# Hub.net
KiCad netlist of a schematic drawn in EAGLE
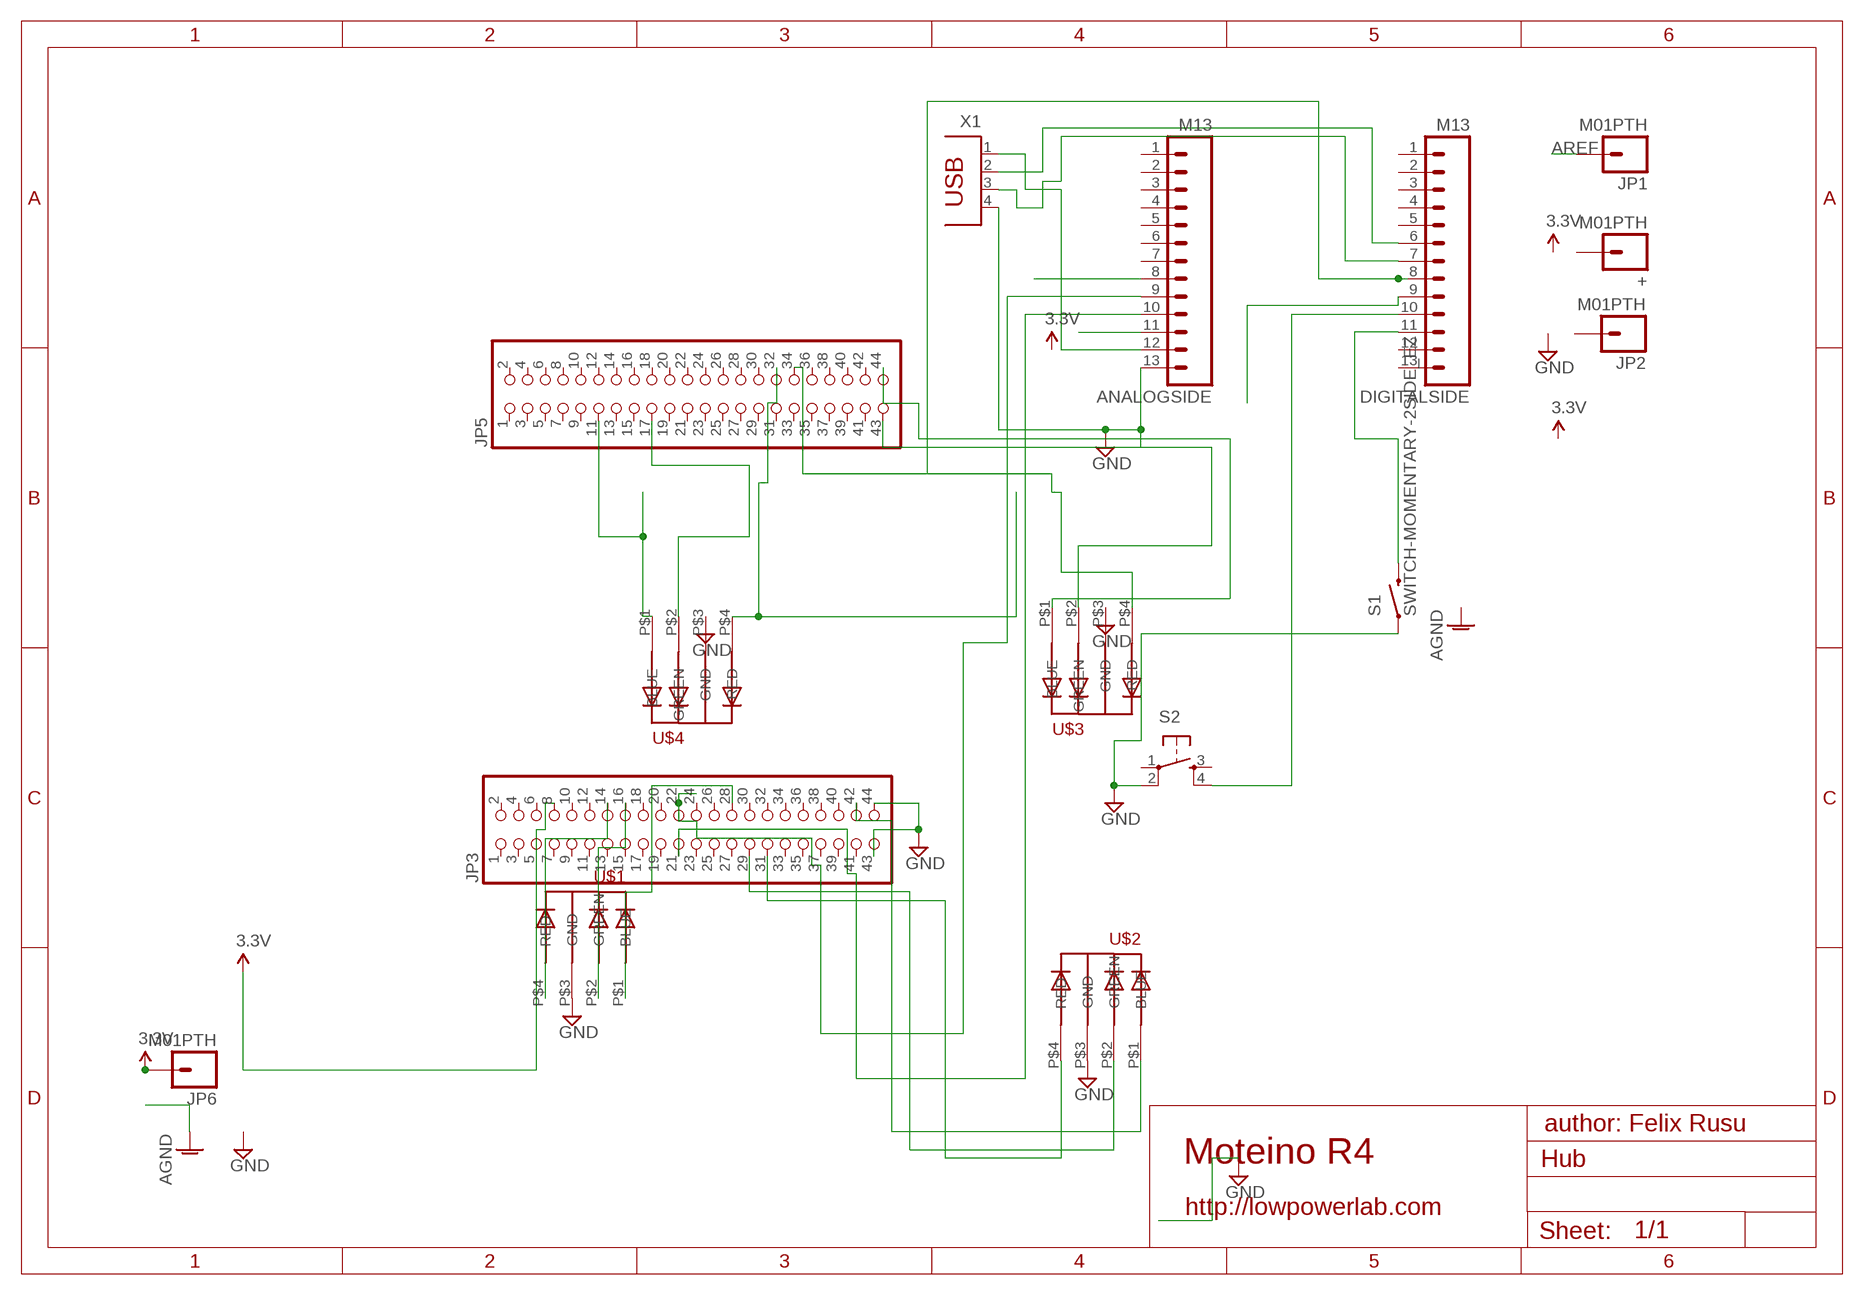
[diagram p0: schematic, sheet 1]

(export (version "E")
  (design (tool "Eeschema 10.0.6"))
  (components
    (comp (ref "+")
      (value "M01PTH")
      (footprint "eagle-import:1X01")
      (libsource (lib "eagle-import") (part "M01PTH"))
    )
    (comp (ref "ANALOGSIDE")
      (value "M13")
      (footprint "eagle-import:1X13")
      (libsource (lib "eagle-import") (part "M13"))
    )
    (comp (ref "DIGITALSIDE")
      (value "M13")
      (footprint "eagle-import:1X13")
      (libsource (lib "eagle-import") (part "M13"))
    )
    (comp (ref "JP1")
      (value "M01PTH")
      (footprint "eagle-import:1X01")
      (libsource (lib "eagle-import") (part "M01PTH"))
    )
    (comp (ref "JP2")
      (value "M01PTH")
      (footprint "eagle-import:1X01")
      (libsource (lib "eagle-import") (part "M01PTH"))
    )
    (comp (ref "JP3")
      (value "PINHD-2X22")
      (footprint "eagle-import:2X22")
      (libsource (lib "eagle-import") (part "PINHD-2X22"))
    )
    (comp (ref "JP5")
      (value "PINHD-2X22")
      (footprint "eagle-import:2X22")
      (libsource (lib "eagle-import") (part "PINHD-2X22"))
    )
    (comp (ref "JP6")
      (value "M01PTH")
      (footprint "eagle-import:1X01")
      (libsource (lib "eagle-import") (part "M01PTH"))
    )
    (comp (ref "S1")
      (value "SWITCH-MOMENTARY-2SIDE_EZ")
      (footprint "eagle-import:TACTILE-PTH-SIDEEZ")
      (libsource (lib "eagle-import") (part "SWITCH-MOMENTARY-2SIDE_EZ"))
    )
    (comp (ref "S2")
      (value "TAC_SWITCHPTH")
      (footprint "eagle-import:TACTILE-PTH")
      (libsource (lib "eagle-import") (part "TAC_SWITCHPTH"))
    )
    (comp (ref "U$1")
      (value "5MMRGBLED")
      (footprint "eagle-import:LED5MMRGB")
      (libsource (lib "eagle-import") (part "5MMRGBLED"))
    )
    (comp (ref "U$2")
      (value "5MMRGBLED")
      (footprint "eagle-import:LED5MMRGB")
      (libsource (lib "eagle-import") (part "5MMRGBLED"))
    )
    (comp (ref "U$3")
      (value "5MMRGBLED")
      (footprint "eagle-import:LED5MMRGB")
      (libsource (lib "eagle-import") (part "5MMRGBLED"))
    )
    (comp (ref "U$4")
      (value "5MMRGBLED")
      (footprint "eagle-import:LED5MMRGB")
      (libsource (lib "eagle-import") (part "5MMRGBLED"))
    )
    (comp (ref "X1")
      (value "PN87520")
      (footprint "eagle-import:PN87520")
      (libsource (lib "eagle-import") (part "PN87520"))
    )
  )
  (nets
    (net (code "1") (name "/AREF") (class "Default")
      (node (ref "JP1") (pin "1") (pinfunction "1_1") (pintype "passive"))
    )
    (net (code "2") (name "3.3V") (class "Default")
      (node (ref "JP3") (pin "8") (pinfunction "8_8") (pintype "passive"))
      (node (ref "JP6") (pin "1") (pinfunction "1_1") (pintype "passive"))
    )
    (net (code "4") (name "GND") (class "Default")
      (node (ref "ANALOGSIDE") (pin "13") (pinfunction "13_13") (pintype "passive"))
      (node (ref "JP3") (pin "43") (pinfunction "43_43") (pintype "passive"))
      (node (ref "JP3") (pin "44") (pinfunction "44_44") (pintype "passive"))
      (node (ref "S1") (pin "1") (pinfunction "1_1") (pintype "passive"))
      (node (ref "S2") (pin "2") (pinfunction "2_2") (pintype "passive"))
      (node (ref "U$1") (pin "P$3") (pinfunction "GND_P$3") (pintype "bidirectional"))
      (node (ref "U$2") (pin "P$3") (pinfunction "GND_P$3") (pintype "bidirectional"))
      (node (ref "U$3") (pin "P$3") (pinfunction "GND_P$3") (pintype "bidirectional"))
      (node (ref "U$4") (pin "P$3") (pinfunction "GND_P$3") (pintype "bidirectional"))
      (node (ref "X1") (pin "4") (pinfunction "4_4") (pintype "passive"))
    )
    (net (code "5") (name "Net-(ANALOGSIDE-Pad9)") (class "Default")
      (node (ref "ANALOGSIDE") (pin "9") (pinfunction "9_9") (pintype "passive"))
      (node (ref "JP3") (pin "22") (pinfunction "22_22") (pintype "passive"))
    )
    (net (code "6") (name "Net-(ANALOGSIDE-Pad10)") (class "Default")
      (node (ref "ANALOGSIDE") (pin "10") (pinfunction "10_10") (pintype "passive"))
      (node (ref "JP3") (pin "21") (pinfunction "21_21") (pintype "passive"))
    )
    (net (code "7") (name "Net-(ANALOGSIDE-Pad12)") (class "Default")
      (node (ref "ANALOGSIDE") (pin "12") (pinfunction "12_12") (pintype "passive"))
      (node (ref "X1") (pin "1") (pinfunction "1_1") (pintype "passive"))
    )
    (net (code "8") (name "Net-(DIGITALSIDE-Pad6)") (class "Default")
      (node (ref "DIGITALSIDE") (pin "6") (pinfunction "6_6") (pintype "passive"))
      (node (ref "X1") (pin "2") (pinfunction "2_2") (pintype "passive"))
    )
    (net (code "9") (name "Net-(DIGITALSIDE-Pad7)") (class "Default")
      (node (ref "DIGITALSIDE") (pin "7") (pinfunction "7_7") (pintype "passive"))
      (node (ref "X1") (pin "3") (pinfunction "3_3") (pintype "passive"))
    )
    (net (code "10") (name "Net-(DIGITALSIDE-Pad10)") (class "Default")
      (node (ref "DIGITALSIDE") (pin "10") (pinfunction "10_10") (pintype "passive"))
      (node (ref "S2") (pin "4") (pinfunction "4_4") (pintype "passive"))
    )
    (net (code "11") (name "Net-(DIGITALSIDE-Pad11)") (class "Default")
      (node (ref "DIGITALSIDE") (pin "11") (pinfunction "11_11") (pintype "passive"))
      (node (ref "S1") (pin "2") (pinfunction "2_2") (pintype "passive"))
    )
    (net (code "12") (name "Net-(U$1-BLUE)") (class "Default")
      (node (ref "JP3") (pin "28") (pinfunction "28_28") (pintype "passive"))
      (node (ref "U$1") (pin "P$1") (pinfunction "BLUE_P$1") (pintype "bidirectional"))
    )
    (net (code "13") (name "Net-(U$1-GREEN)") (class "Default")
      (node (ref "JP3") (pin "16") (pinfunction "16_16") (pintype "passive"))
      (node (ref "U$1") (pin "P$2") (pinfunction "GREEN_P$2") (pintype "bidirectional"))
    )
    (net (code "14") (name "Net-(U$1-RED)") (class "Default")
      (node (ref "JP3") (pin "14") (pinfunction "14_14") (pintype "passive"))
      (node (ref "U$1") (pin "P$4") (pinfunction "RED_P$4") (pintype "bidirectional"))
    )
    (net (code "15") (name "Net-(U$2-BLUE)") (class "Default")
      (node (ref "JP3") (pin "42") (pinfunction "42_42") (pintype "passive"))
      (node (ref "U$2") (pin "P$1") (pinfunction "BLUE_P$1") (pintype "bidirectional"))
    )
    (net (code "16") (name "Net-(U$2-GREEN)") (class "Default")
      (node (ref "JP3") (pin "29") (pinfunction "29_29") (pintype "passive"))
      (node (ref "U$2") (pin "P$2") (pinfunction "GREEN_P$2") (pintype "bidirectional"))
    )
    (net (code "17") (name "Net-(U$2-RED)") (class "Default")
      (node (ref "JP3") (pin "31") (pinfunction "31_31") (pintype "passive"))
      (node (ref "U$2") (pin "P$4") (pinfunction "RED_P$4") (pintype "bidirectional"))
    )
    (net (code "18") (name "Net-(U$3-BLUE)") (class "Default")
      (node (ref "JP5") (pin "44") (pinfunction "44_44") (pintype "passive"))
      (node (ref "U$3") (pin "P$1") (pinfunction "BLUE_P$1") (pintype "bidirectional"))
    )
    (net (code "19") (name "Net-(U$3-GREEN)") (class "Default")
      (node (ref "JP5") (pin "43") (pinfunction "43_43") (pintype "passive"))
      (node (ref "U$3") (pin "P$2") (pinfunction "GREEN_P$2") (pintype "bidirectional"))
    )
    (net (code "20") (name "Net-(U$3-RED)") (class "Default")
      (node (ref "JP5") (pin "34") (pinfunction "34_34") (pintype "passive"))
      (node (ref "U$3") (pin "P$4") (pinfunction "RED_P$4") (pintype "bidirectional"))
    )
    (net (code "21") (name "Net-(U$4-BLUE)") (class "Default")
      (node (ref "JP5") (pin "11") (pinfunction "11_11") (pintype "passive"))
      (node (ref "U$4") (pin "P$1") (pinfunction "BLUE_P$1") (pintype "bidirectional"))
    )
    (net (code "22") (name "Net-(U$4-GREEN)") (class "Default")
      (node (ref "JP5") (pin "17") (pinfunction "17_17") (pintype "passive"))
      (node (ref "U$4") (pin "P$2") (pinfunction "GREEN_P$2") (pintype "bidirectional"))
    )
    (net (code "23") (name "Net-(U$4-RED)") (class "Default")
      (node (ref "JP5") (pin "32") (pinfunction "32_32") (pintype "passive"))
      (node (ref "U$4") (pin "P$4") (pinfunction "RED_P$4") (pintype "bidirectional"))
    )
    (net (code "24") (name "unconnected-(+-Pad1)") (class "Default")
      (node (ref "+") (pin "1") (pinfunction "1_1") (pintype "passive"))
    )
    (net (code "25") (name "unconnected-(ANALOGSIDE-Pad1)") (class "Default")
      (node (ref "ANALOGSIDE") (pin "1") (pinfunction "1_1") (pintype "passive"))
    )
    (net (code "26") (name "unconnected-(ANALOGSIDE-Pad2)") (class "Default")
      (node (ref "ANALOGSIDE") (pin "2") (pinfunction "2_2") (pintype "passive"))
    )
    (net (code "27") (name "unconnected-(ANALOGSIDE-Pad3)") (class "Default")
      (node (ref "ANALOGSIDE") (pin "3") (pinfunction "3_3") (pintype "passive"))
    )
    (net (code "28") (name "unconnected-(ANALOGSIDE-Pad4)") (class "Default")
      (node (ref "ANALOGSIDE") (pin "4") (pinfunction "4_4") (pintype "passive"))
    )
    (net (code "29") (name "unconnected-(ANALOGSIDE-Pad5)") (class "Default")
      (node (ref "ANALOGSIDE") (pin "5") (pinfunction "5_5") (pintype "passive"))
    )
    (net (code "30") (name "unconnected-(ANALOGSIDE-Pad6)") (class "Default")
      (node (ref "ANALOGSIDE") (pin "6") (pinfunction "6_6") (pintype "passive"))
    )
    (net (code "31") (name "unconnected-(ANALOGSIDE-Pad7)") (class "Default")
      (node (ref "ANALOGSIDE") (pin "7") (pinfunction "7_7") (pintype "passive"))
    )
    (net (code "32") (name "unconnected-(ANALOGSIDE-Pad8)") (class "Default")
      (node (ref "ANALOGSIDE") (pin "8") (pinfunction "8_8") (pintype "passive"))
    )
    (net (code "33") (name "unconnected-(ANALOGSIDE-Pad11)") (class "Default")
      (node (ref "ANALOGSIDE") (pin "11") (pinfunction "11_11") (pintype "passive"))
    )
    (net (code "34") (name "unconnected-(DIGITALSIDE-Pad1)") (class "Default")
      (node (ref "DIGITALSIDE") (pin "1") (pinfunction "1_1") (pintype "passive"))
    )
    (net (code "35") (name "unconnected-(DIGITALSIDE-Pad2)") (class "Default")
      (node (ref "DIGITALSIDE") (pin "2") (pinfunction "2_2") (pintype "passive"))
    )
    (net (code "36") (name "unconnected-(DIGITALSIDE-Pad3)") (class "Default")
      (node (ref "DIGITALSIDE") (pin "3") (pinfunction "3_3") (pintype "passive"))
    )
    (net (code "37") (name "unconnected-(DIGITALSIDE-Pad4)") (class "Default")
      (node (ref "DIGITALSIDE") (pin "4") (pinfunction "4_4") (pintype "passive"))
    )
    (net (code "38") (name "unconnected-(DIGITALSIDE-Pad5)") (class "Default")
      (node (ref "DIGITALSIDE") (pin "5") (pinfunction "5_5") (pintype "passive"))
    )
    (net (code "39") (name "unconnected-(DIGITALSIDE-Pad8)") (class "Default")
      (node (ref "DIGITALSIDE") (pin "8") (pinfunction "8_8") (pintype "passive"))
    )
    (net (code "40") (name "unconnected-(DIGITALSIDE-Pad9)") (class "Default")
      (node (ref "DIGITALSIDE") (pin "9") (pinfunction "9_9") (pintype "passive"))
    )
    (net (code "41") (name "unconnected-(DIGITALSIDE-Pad12)") (class "Default")
      (node (ref "DIGITALSIDE") (pin "12") (pinfunction "12_12") (pintype "passive"))
    )
    (net (code "42") (name "unconnected-(DIGITALSIDE-Pad13)") (class "Default")
      (node (ref "DIGITALSIDE") (pin "13") (pinfunction "13_13") (pintype "passive"))
    )
    (net (code "43") (name "unconnected-(JP2-Pad1)") (class "Default")
      (node (ref "JP2") (pin "1") (pinfunction "1_1") (pintype "passive"))
    )
    (net (code "44") (name "unconnected-(JP3-Pad1)") (class "Default")
      (node (ref "JP3") (pin "1") (pinfunction "1_1") (pintype "passive"))
    )
    (net (code "45") (name "unconnected-(JP3-Pad2)") (class "Default")
      (node (ref "JP3") (pin "2") (pinfunction "2_2") (pintype "passive"))
    )
    (net (code "46") (name "unconnected-(JP3-Pad3)") (class "Default")
      (node (ref "JP3") (pin "3") (pinfunction "3_3") (pintype "passive"))
    )
    (net (code "47") (name "unconnected-(JP3-Pad4)") (class "Default")
      (node (ref "JP3") (pin "4") (pinfunction "4_4") (pintype "passive"))
    )
    (net (code "48") (name "unconnected-(JP3-Pad5)") (class "Default")
      (node (ref "JP3") (pin "5") (pinfunction "5_5") (pintype "passive"))
    )
    (net (code "49") (name "unconnected-(JP3-Pad6)") (class "Default")
      (node (ref "JP3") (pin "6") (pinfunction "6_6") (pintype "passive"))
    )
    (net (code "50") (name "unconnected-(JP3-Pad7)") (class "Default")
      (node (ref "JP3") (pin "7") (pinfunction "7_7") (pintype "passive"))
    )
    (net (code "51") (name "unconnected-(JP3-Pad9)") (class "Default")
      (node (ref "JP3") (pin "9") (pinfunction "9_9") (pintype "passive"))
    )
    (net (code "52") (name "unconnected-(JP3-Pad10)") (class "Default")
      (node (ref "JP3") (pin "10") (pinfunction "10_10") (pintype "passive"))
    )
    (net (code "53") (name "unconnected-(JP3-Pad11)") (class "Default")
      (node (ref "JP3") (pin "11") (pinfunction "11_11") (pintype "passive"))
    )
    (net (code "54") (name "unconnected-(JP3-Pad12)") (class "Default")
      (node (ref "JP3") (pin "12") (pinfunction "12_12") (pintype "passive"))
    )
    (net (code "55") (name "unconnected-(JP3-Pad13)") (class "Default")
      (node (ref "JP3") (pin "13") (pinfunction "13_13") (pintype "passive"))
    )
    (net (code "56") (name "unconnected-(JP3-Pad15)") (class "Default")
      (node (ref "JP3") (pin "15") (pinfunction "15_15") (pintype "passive"))
    )
    (net (code "57") (name "unconnected-(JP3-Pad17)") (class "Default")
      (node (ref "JP3") (pin "17") (pinfunction "17_17") (pintype "passive"))
    )
    (net (code "58") (name "unconnected-(JP3-Pad18)") (class "Default")
      (node (ref "JP3") (pin "18") (pinfunction "18_18") (pintype "passive"))
    )
    (net (code "59") (name "unconnected-(JP3-Pad19)") (class "Default")
      (node (ref "JP3") (pin "19") (pinfunction "19_19") (pintype "passive"))
    )
    (net (code "60") (name "unconnected-(JP3-Pad20)") (class "Default")
      (node (ref "JP3") (pin "20") (pinfunction "20_20") (pintype "passive"))
    )
    (net (code "61") (name "unconnected-(JP3-Pad23)") (class "Default")
      (node (ref "JP3") (pin "23") (pinfunction "23_23") (pintype "passive"))
    )
    (net (code "62") (name "unconnected-(JP3-Pad24)") (class "Default")
      (node (ref "JP3") (pin "24") (pinfunction "24_24") (pintype "passive"))
    )
    (net (code "63") (name "unconnected-(JP3-Pad25)") (class "Default")
      (node (ref "JP3") (pin "25") (pinfunction "25_25") (pintype "passive"))
    )
    (net (code "64") (name "unconnected-(JP3-Pad26)") (class "Default")
      (node (ref "JP3") (pin "26") (pinfunction "26_26") (pintype "passive"))
    )
    (net (code "65") (name "unconnected-(JP3-Pad27)") (class "Default")
      (node (ref "JP3") (pin "27") (pinfunction "27_27") (pintype "passive"))
    )
    (net (code "66") (name "unconnected-(JP3-Pad30)") (class "Default")
      (node (ref "JP3") (pin "30") (pinfunction "30_30") (pintype "passive"))
    )
    (net (code "67") (name "unconnected-(JP3-Pad32)") (class "Default")
      (node (ref "JP3") (pin "32") (pinfunction "32_32") (pintype "passive"))
    )
    (net (code "68") (name "unconnected-(JP3-Pad33)") (class "Default")
      (node (ref "JP3") (pin "33") (pinfunction "33_33") (pintype "passive"))
    )
    (net (code "69") (name "unconnected-(JP3-Pad34)") (class "Default")
      (node (ref "JP3") (pin "34") (pinfunction "34_34") (pintype "passive"))
    )
    (net (code "70") (name "unconnected-(JP3-Pad35)") (class "Default")
      (node (ref "JP3") (pin "35") (pinfunction "35_35") (pintype "passive"))
    )
    (net (code "71") (name "unconnected-(JP3-Pad36)") (class "Default")
      (node (ref "JP3") (pin "36") (pinfunction "36_36") (pintype "passive"))
    )
    (net (code "72") (name "unconnected-(JP3-Pad37)") (class "Default")
      (node (ref "JP3") (pin "37") (pinfunction "37_37") (pintype "passive"))
    )
    (net (code "73") (name "unconnected-(JP3-Pad38)") (class "Default")
      (node (ref "JP3") (pin "38") (pinfunction "38_38") (pintype "passive"))
    )
    (net (code "74") (name "unconnected-(JP3-Pad39)") (class "Default")
      (node (ref "JP3") (pin "39") (pinfunction "39_39") (pintype "passive"))
    )
    (net (code "75") (name "unconnected-(JP3-Pad40)") (class "Default")
      (node (ref "JP3") (pin "40") (pinfunction "40_40") (pintype "passive"))
    )
    (net (code "76") (name "unconnected-(JP3-Pad41)") (class "Default")
      (node (ref "JP3") (pin "41") (pinfunction "41_41") (pintype "passive"))
    )
    (net (code "77") (name "unconnected-(JP5-Pad1)") (class "Default")
      (node (ref "JP5") (pin "1") (pinfunction "1_1") (pintype "passive"))
    )
    (net (code "78") (name "unconnected-(JP5-Pad2)") (class "Default")
      (node (ref "JP5") (pin "2") (pinfunction "2_2") (pintype "passive"))
    )
    (net (code "79") (name "unconnected-(JP5-Pad3)") (class "Default")
      (node (ref "JP5") (pin "3") (pinfunction "3_3") (pintype "passive"))
    )
    (net (code "80") (name "unconnected-(JP5-Pad4)") (class "Default")
      (node (ref "JP5") (pin "4") (pinfunction "4_4") (pintype "passive"))
    )
    (net (code "81") (name "unconnected-(JP5-Pad5)") (class "Default")
      (node (ref "JP5") (pin "5") (pinfunction "5_5") (pintype "passive"))
    )
    (net (code "82") (name "unconnected-(JP5-Pad6)") (class "Default")
      (node (ref "JP5") (pin "6") (pinfunction "6_6") (pintype "passive"))
    )
    (net (code "83") (name "unconnected-(JP5-Pad7)") (class "Default")
      (node (ref "JP5") (pin "7") (pinfunction "7_7") (pintype "passive"))
    )
    (net (code "84") (name "unconnected-(JP5-Pad8)") (class "Default")
      (node (ref "JP5") (pin "8") (pinfunction "8_8") (pintype "passive"))
    )
    (net (code "85") (name "unconnected-(JP5-Pad9)") (class "Default")
      (node (ref "JP5") (pin "9") (pinfunction "9_9") (pintype "passive"))
    )
    (net (code "86") (name "unconnected-(JP5-Pad10)") (class "Default")
      (node (ref "JP5") (pin "10") (pinfunction "10_10") (pintype "passive"))
    )
    (net (code "87") (name "unconnected-(JP5-Pad12)") (class "Default")
      (node (ref "JP5") (pin "12") (pinfunction "12_12") (pintype "passive"))
    )
    (net (code "88") (name "unconnected-(JP5-Pad13)") (class "Default")
      (node (ref "JP5") (pin "13") (pinfunction "13_13") (pintype "passive"))
    )
    (net (code "89") (name "unconnected-(JP5-Pad14)") (class "Default")
      (node (ref "JP5") (pin "14") (pinfunction "14_14") (pintype "passive"))
    )
    (net (code "90") (name "unconnected-(JP5-Pad15)") (class "Default")
      (node (ref "JP5") (pin "15") (pinfunction "15_15") (pintype "passive"))
    )
    (net (code "91") (name "unconnected-(JP5-Pad16)") (class "Default")
      (node (ref "JP5") (pin "16") (pinfunction "16_16") (pintype "passive"))
    )
    (net (code "92") (name "unconnected-(JP5-Pad18)") (class "Default")
      (node (ref "JP5") (pin "18") (pinfunction "18_18") (pintype "passive"))
    )
    (net (code "93") (name "unconnected-(JP5-Pad19)") (class "Default")
      (node (ref "JP5") (pin "19") (pinfunction "19_19") (pintype "passive"))
    )
    (net (code "94") (name "unconnected-(JP5-Pad20)") (class "Default")
      (node (ref "JP5") (pin "20") (pinfunction "20_20") (pintype "passive"))
    )
    (net (code "95") (name "unconnected-(JP5-Pad21)") (class "Default")
      (node (ref "JP5") (pin "21") (pinfunction "21_21") (pintype "passive"))
    )
    (net (code "96") (name "unconnected-(JP5-Pad22)") (class "Default")
      (node (ref "JP5") (pin "22") (pinfunction "22_22") (pintype "passive"))
    )
    (net (code "97") (name "unconnected-(JP5-Pad23)") (class "Default")
      (node (ref "JP5") (pin "23") (pinfunction "23_23") (pintype "passive"))
    )
    (net (code "98") (name "unconnected-(JP5-Pad24)") (class "Default")
      (node (ref "JP5") (pin "24") (pinfunction "24_24") (pintype "passive"))
    )
    (net (code "99") (name "unconnected-(JP5-Pad25)") (class "Default")
      (node (ref "JP5") (pin "25") (pinfunction "25_25") (pintype "passive"))
    )
    (net (code "100") (name "unconnected-(JP5-Pad26)") (class "Default")
      (node (ref "JP5") (pin "26") (pinfunction "26_26") (pintype "passive"))
    )
    (net (code "101") (name "unconnected-(JP5-Pad27)") (class "Default")
      (node (ref "JP5") (pin "27") (pinfunction "27_27") (pintype "passive"))
    )
    (net (code "102") (name "unconnected-(JP5-Pad28)") (class "Default")
      (node (ref "JP5") (pin "28") (pinfunction "28_28") (pintype "passive"))
    )
    (net (code "103") (name "unconnected-(JP5-Pad29)") (class "Default")
      (node (ref "JP5") (pin "29") (pinfunction "29_29") (pintype "passive"))
    )
    (net (code "104") (name "unconnected-(JP5-Pad30)") (class "Default")
      (node (ref "JP5") (pin "30") (pinfunction "30_30") (pintype "passive"))
    )
    (net (code "105") (name "unconnected-(JP5-Pad31)") (class "Default")
      (node (ref "JP5") (pin "31") (pinfunction "31_31") (pintype "passive"))
    )
    (net (code "106") (name "unconnected-(JP5-Pad33)") (class "Default")
      (node (ref "JP5") (pin "33") (pinfunction "33_33") (pintype "passive"))
    )
    (net (code "107") (name "unconnected-(JP5-Pad35)") (class "Default")
      (node (ref "JP5") (pin "35") (pinfunction "35_35") (pintype "passive"))
    )
    (net (code "108") (name "unconnected-(JP5-Pad36)") (class "Default")
      (node (ref "JP5") (pin "36") (pinfunction "36_36") (pintype "passive"))
    )
    (net (code "109") (name "unconnected-(JP5-Pad37)") (class "Default")
      (node (ref "JP5") (pin "37") (pinfunction "37_37") (pintype "passive"))
    )
    (net (code "110") (name "unconnected-(JP5-Pad38)") (class "Default")
      (node (ref "JP5") (pin "38") (pinfunction "38_38") (pintype "passive"))
    )
    (net (code "111") (name "unconnected-(JP5-Pad39)") (class "Default")
      (node (ref "JP5") (pin "39") (pinfunction "39_39") (pintype "passive"))
    )
    (net (code "112") (name "unconnected-(JP5-Pad40)") (class "Default")
      (node (ref "JP5") (pin "40") (pinfunction "40_40") (pintype "passive"))
    )
    (net (code "113") (name "unconnected-(JP5-Pad41)") (class "Default")
      (node (ref "JP5") (pin "41") (pinfunction "41_41") (pintype "passive"))
    )
    (net (code "114") (name "unconnected-(JP5-Pad42)") (class "Default")
      (node (ref "JP5") (pin "42") (pinfunction "42_42") (pintype "passive"))
    )
    (net (code "115") (name "unconnected-(S2-Pad1)") (class "Default")
      (node (ref "S2") (pin "1") (pinfunction "1_1") (pintype "passive"))
    )
    (net (code "116") (name "unconnected-(S2-Pad3)") (class "Default")
      (node (ref "S2") (pin "3") (pinfunction "3_3") (pintype "passive"))
    )
  )
)
